# led_control.net
KiCad netlist of a schematic drawn in Altium Designer
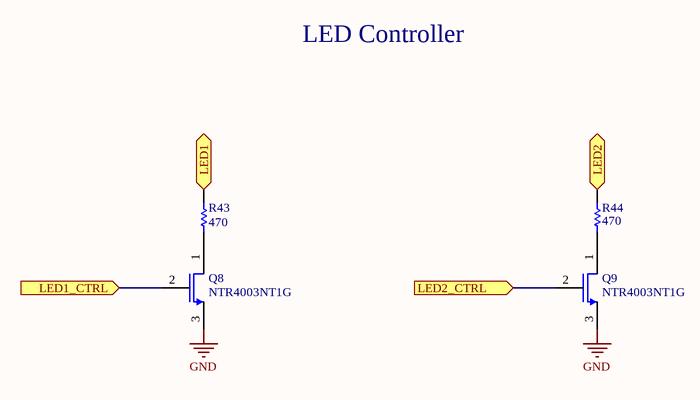
[diagram p0: led_control.SchDoc]

(export (version "E")
  (design (tool "Eeschema 10.0.6"))
  (components
    (comp (ref "Q8")
      (value "NTR4003NT1G")
      (footprint "SOT-23")
      (description "MOSFET N-CH 30V 500MA SOT-23")
      (fields (field (name "MANUFACTURER") "ON Semiconductor"))
      (libsource (lib "common") (part "NTR4003NT1G"))
    )
    (comp (ref "Q9")
      (value "NTR4003NT1G")
      (footprint "SOT-23")
      (description "MOSFET N-CH 30V 500MA SOT-23")
      (fields (field (name "MANUFACTURER") "ON Semiconductor"))
      (libsource (lib "common") (part "NTR4003NT1G"))
    )
    (comp (ref "R43")
      (value "470")
      (footprint "RESC1608N")
      (description "Resistor")
      (fields
        (field (name "MANUFACTURER") "Yageo")
        (field (name "MANUFACTURER PART NUMBER") "RC0603JR-07470RL")
        (field (name "PUBLISHER") "Altium Limited")
      )
      (libsource (lib "Miscellaneous Devices") (part "Res1"))
    )
    (comp (ref "R44")
      (value "470")
      (footprint "RESC1608N")
      (description "Resistor")
      (fields
        (field (name "MANUFACTURER") "Yageo")
        (field (name "MANUFACTURER PART NUMBER") "RC0603JR-07470RL")
        (field (name "PUBLISHER") "Altium Limited")
      )
      (libsource (lib "Miscellaneous Devices") (part "Res1"))
    )
  )
  (nets
    (net (code "1") (name "/LED1") (class "Default")
      (node (ref "R43") (pin "1") (pinfunction "1_1") (pintype "passive"))
    )
    (net (code "2") (name "/LED1_CTRL") (class "Default")
      (node (ref "Q8") (pin "2") (pinfunction "2_2") (pintype "passive"))
    )
    (net (code "3") (name "/LED2") (class "Default")
      (node (ref "R44") (pin "2") (pinfunction "2_2") (pintype "passive"))
    )
    (net (code "4") (name "/LED2_CTRL") (class "Default")
      (node (ref "Q9") (pin "2") (pinfunction "2_2") (pintype "passive"))
    )
    (net (code "5") (name "GND") (class "Default")
      (node (ref "Q8") (pin "3") (pinfunction "3_3") (pintype "passive"))
      (node (ref "Q9") (pin "3") (pinfunction "3_3") (pintype "passive"))
    )
    (net (code "6") (name "Net-(Q8-Pad1)") (class "Default")
      (node (ref "Q8") (pin "1") (pinfunction "1_1") (pintype "passive"))
      (node (ref "R43") (pin "2") (pinfunction "2_2") (pintype "passive"))
    )
    (net (code "7") (name "Net-(Q9-Pad1)") (class "Default")
      (node (ref "Q9") (pin "1") (pinfunction "1_1") (pintype "passive"))
      (node (ref "R44") (pin "1") (pinfunction "1_1") (pintype "passive"))
    )
  )
)
